# rapidshark-dart-detector-mk-1_1.net
KiCad netlist of a schematic drawn in EAGLE
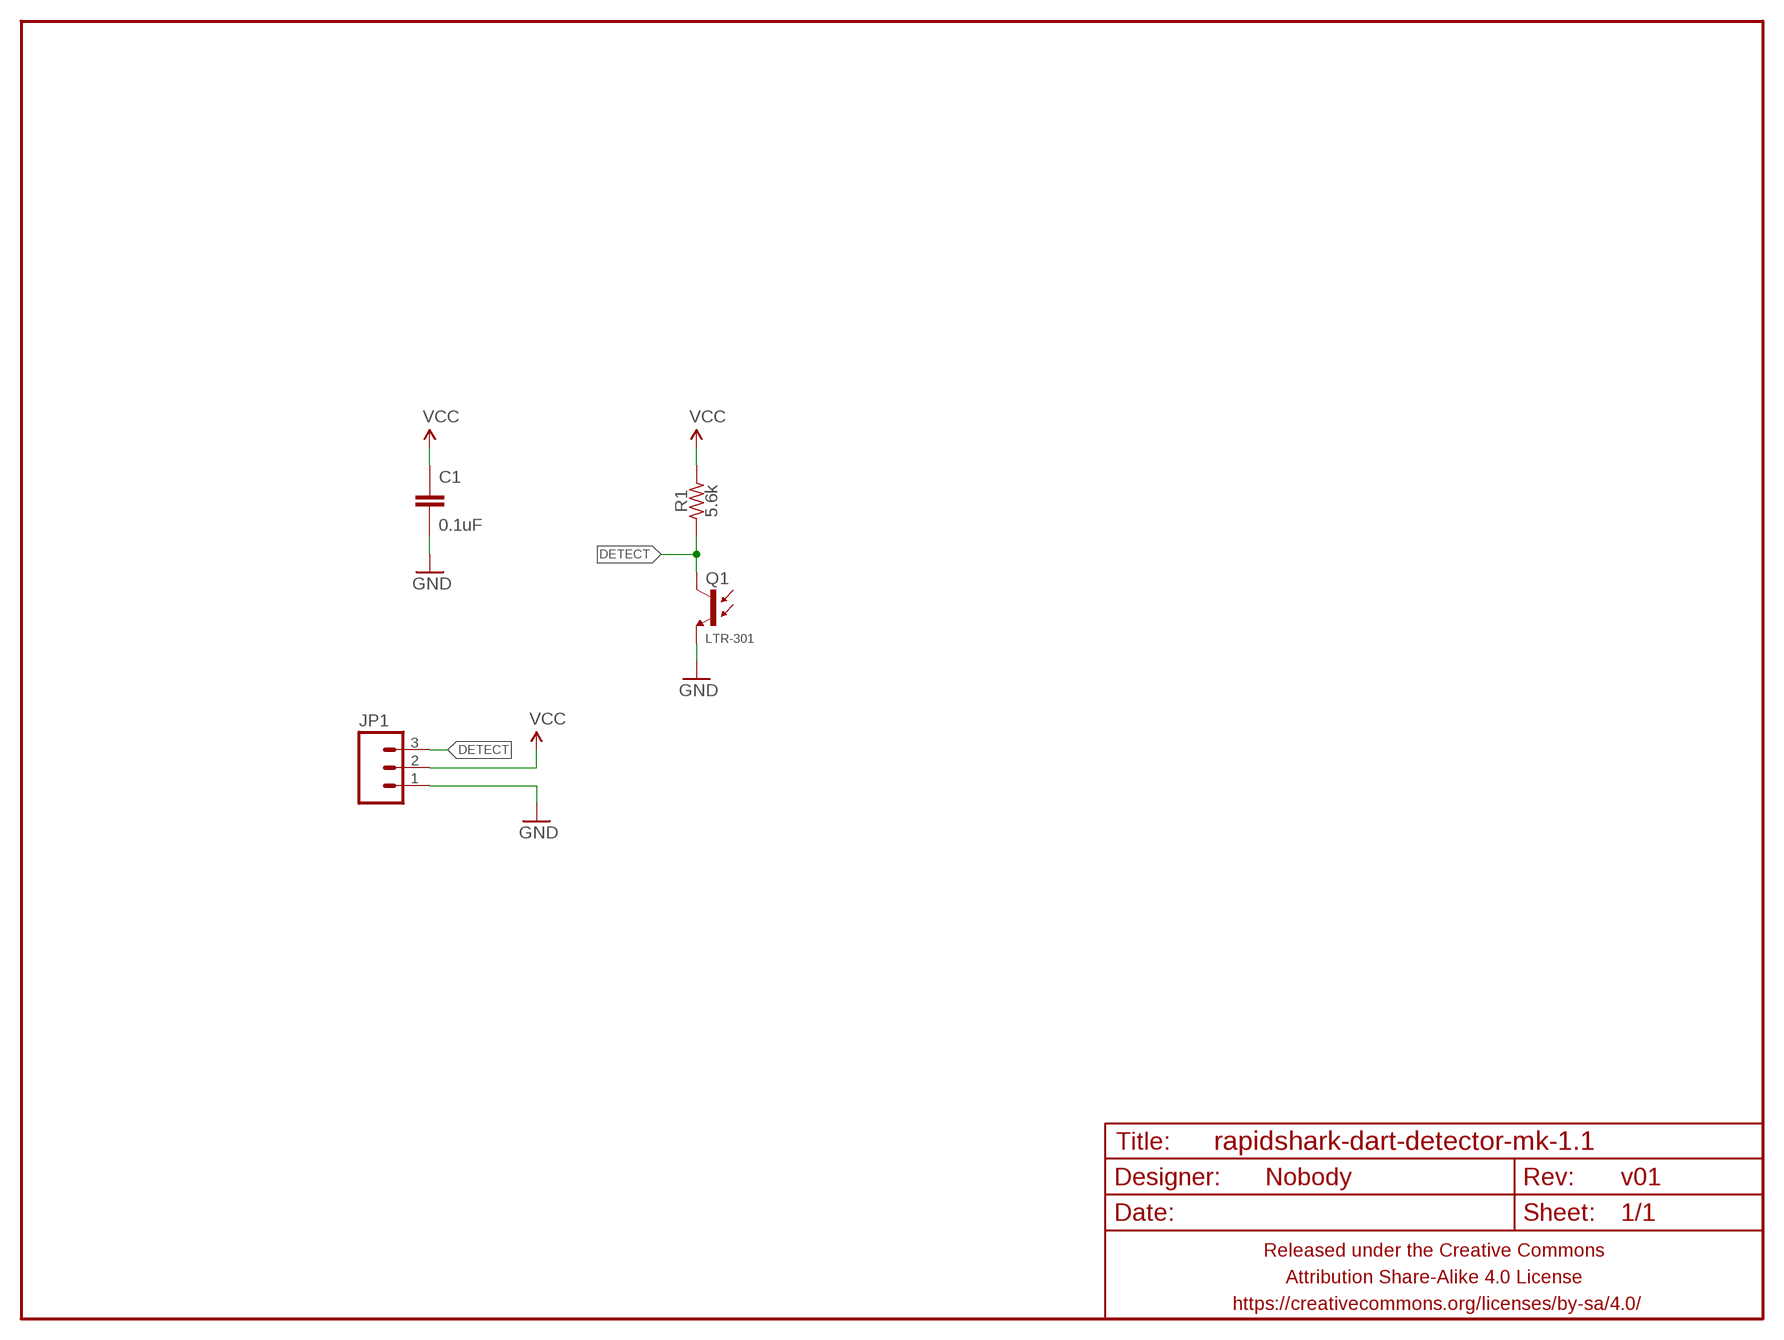
[diagram p0: schematic, sheet 1]

(export (version "E")
  (design (tool "Eeschema 10.0.6"))
  (components
    (comp (ref "C1")
      (value "0.1uF")
      (footprint "eagle-import:C025-024X044")
      (libsource (lib "eagle-import") (part "CAPACITOR-CERAMIC025-024X044"))
    )
    (comp (ref "FRAME1")
      (value "FRAME-LETTERNO_PACKAGE")
      (footprint "eagle-import:DUMMY")
      (fields (field (name "DESIGNER") "Nobody"))
      (libsource (lib "eagle-import") (part "FRAME-LETTERNO_PACKAGE"))
    )
    (comp (ref "JP1")
      (value "M03JST-PTH")
      (footprint "eagle-import:JST-3-PH-RA-PTH")
      (libsource (lib "eagle-import") (part "M03JST-PTH"))
    )
    (comp (ref "Q1")
      (value "LTR-301")
      (footprint "eagle-import:LED-2.54MM-SIDE")
      (libsource (lib "eagle-import") (part "PHOTOTRANSISTOR2.54MM-SIDE"))
    )
    (comp (ref "R1")
      (value "5.6k")
      (footprint "eagle-import:RESISTOR-AXIAL-PTH-6.35MM")
      (libsource (lib "eagle-import") (part "RESISTORPTH-AXIAL-6.35MM"))
    )
  )
  (nets
    (net (code "1") (name "DETECT") (class "Default")
      (node (ref "JP1") (pin "3") (pinfunction "3_3") (pintype "passive"))
      (node (ref "Q1") (pin "A") (pinfunction "C_A") (pintype "bidirectional"))
      (node (ref "R1") (pin "P$1") (pinfunction "1_P$1") (pintype "passive"))
    )
    (net (code "2") (name "GND") (class "Default")
      (node (ref "C1") (pin "2") (pinfunction "2_2") (pintype "passive"))
      (node (ref "JP1") (pin "1") (pinfunction "1_1") (pintype "passive"))
      (node (ref "Q1") (pin "K") (pinfunction "E_K") (pintype "bidirectional"))
    )
    (net (code "3") (name "VCC") (class "Default")
      (node (ref "C1") (pin "1") (pinfunction "1_1") (pintype "passive"))
      (node (ref "JP1") (pin "2") (pinfunction "2_2") (pintype "passive"))
      (node (ref "R1") (pin "P$2") (pinfunction "2_P$2") (pintype "passive"))
    )
  )
)
